# 1u_debug_breakout.net
KiCad netlist of a schematic drawn in EAGLE
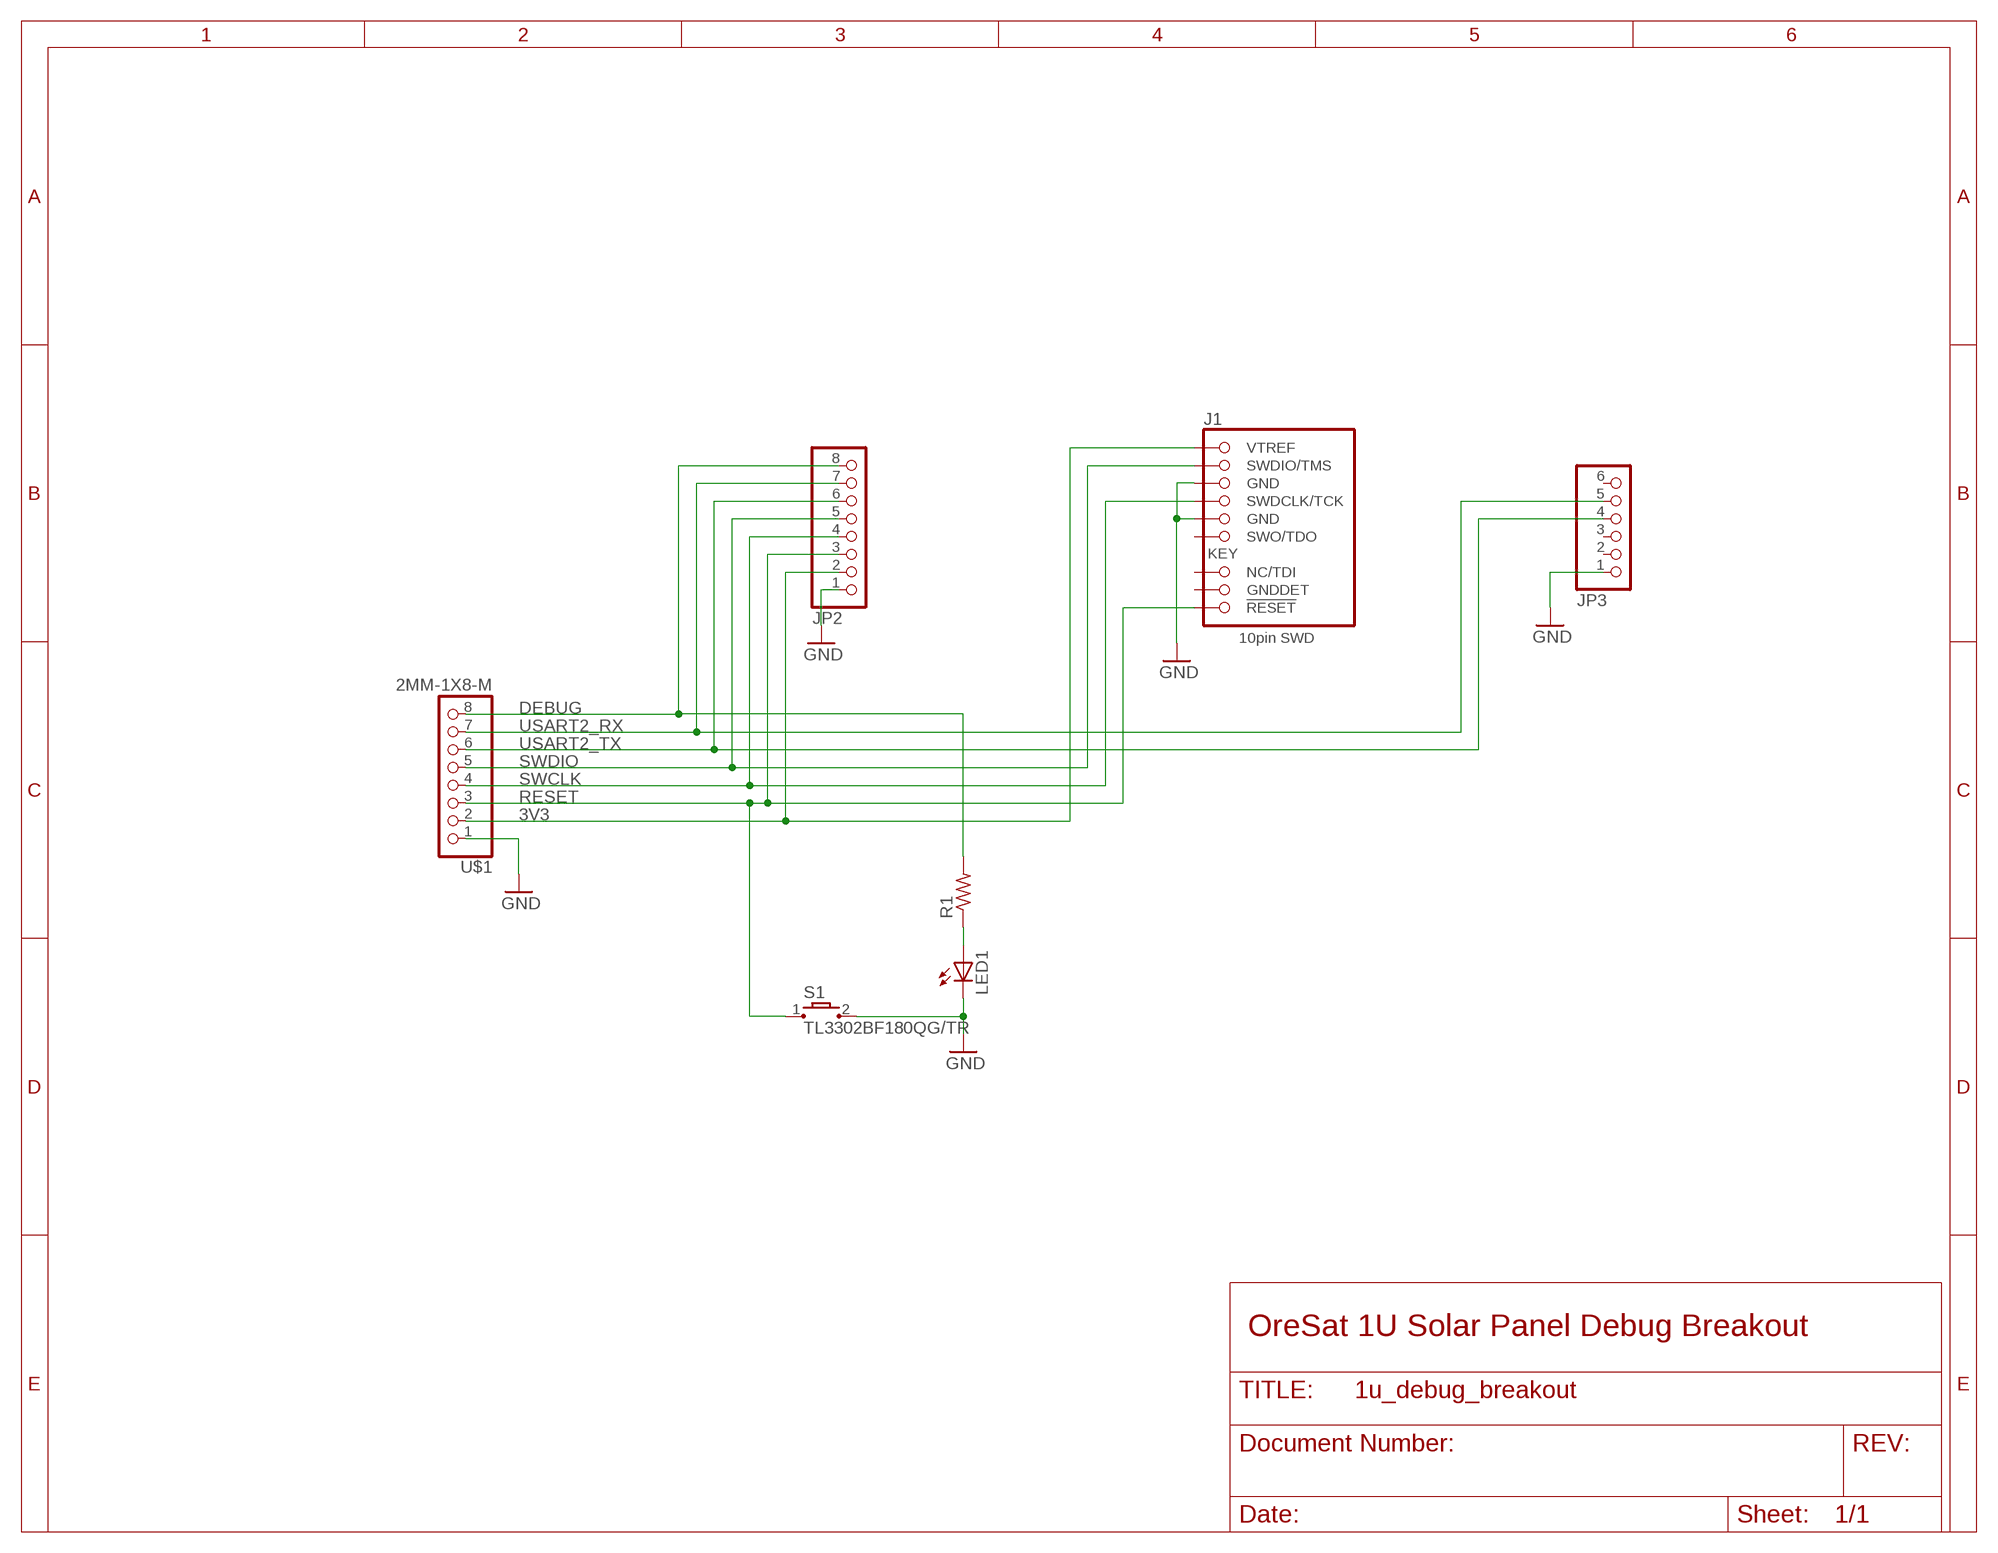
[diagram p0: schematic, sheet 1]

(export (version "E")
  (design (tool "Eeschema 10.0.6"))
  (components
    (comp (ref "J1")
      (value "1.27MM-SWD-CONNECTOR")
      (footprint "eagle-import:1.27MM_2X5")
      (libsource (lib "eagle-import") (part "1.27MM-SWD-CONNECTOR"))
    )
    (comp (ref "JP2")
      (value "PINHD-1X8")
      (footprint "eagle-import:1X08")
      (libsource (lib "eagle-import") (part "PINHD-1X8"))
    )
    (comp (ref "JP3")
      (value "PINHD-1X6")
      (footprint "eagle-import:1X06")
      (libsource (lib "eagle-import") (part "PINHD-1X6"))
    )
    (comp (ref "LED1")
      (value "LEDCHIPLED_0603")
      (footprint "eagle-import:CHIPLED_0603")
      (libsource (lib "eagle-import") (part "LEDCHIPLED_0603"))
    )
    (comp (ref "R1")
      (value "R-US_R0603")
      (footprint "eagle-import:R0603")
      (libsource (lib "eagle-import") (part "R-US_R0603"))
    )
    (comp (ref "S1")
      (value "TL3302BF180QG/TR")
      (footprint "eagle-import:TL3302_GULL_WING")
      (libsource (lib "eagle-import") (part "TL3302-G"))
    )
    (comp (ref "U$1")
      (value "2MM-1X8-M")
      (footprint "eagle-import:CF-2MM-1X8-PRECIDIP-880")
      (libsource (lib "eagle-import") (part "2MM-1X8-M"))
    )
  )
  (nets
    (net (code "1") (name "/3V3") (class "Default")
      (node (ref "J1") (pin "VTREF") (pinfunction "VTREF_VTREF") (pintype "passive"))
      (node (ref "JP2") (pin "2") (pinfunction "2_2") (pintype "passive"))
      (node (ref "U$1") (pin "2") (pinfunction "2_2") (pintype "passive"))
    )
    (net (code "2") (name "/DEBUG") (class "Default")
      (node (ref "JP2") (pin "8") (pinfunction "8_8") (pintype "passive"))
      (node (ref "R1") (pin "2") (pinfunction "2_2") (pintype "passive"))
      (node (ref "U$1") (pin "8") (pinfunction "8_8") (pintype "passive"))
    )
    (net (code "3") (name "/RESET") (class "Default")
      (node (ref "J1") (pin "!RESET") (pinfunction "~{RESET}_!RESET") (pintype "passive"))
      (node (ref "JP2") (pin "3") (pinfunction "3_3") (pintype "passive"))
      (node (ref "S1") (pin "1") (pinfunction "1_1") (pintype "passive"))
      (node (ref "U$1") (pin "3") (pinfunction "3_3") (pintype "passive"))
    )
    (net (code "4") (name "/SWCLK") (class "Default")
      (node (ref "J1") (pin "SWDCLK") (pinfunction "SWDCLK/TCK_SWDCLK") (pintype "passive"))
      (node (ref "JP2") (pin "4") (pinfunction "4_4") (pintype "passive"))
      (node (ref "U$1") (pin "4") (pinfunction "4_4") (pintype "passive"))
    )
    (net (code "5") (name "/SWDIO") (class "Default")
      (node (ref "J1") (pin "SWDIO") (pinfunction "SWDIO/TMS_SWDIO") (pintype "passive"))
      (node (ref "JP2") (pin "5") (pinfunction "5_5") (pintype "passive"))
      (node (ref "U$1") (pin "5") (pinfunction "5_5") (pintype "passive"))
    )
    (net (code "6") (name "/USART2_RX") (class "Default")
      (node (ref "JP2") (pin "7") (pinfunction "7_7") (pintype "passive"))
      (node (ref "JP3") (pin "5") (pinfunction "5_5") (pintype "passive"))
      (node (ref "U$1") (pin "7") (pinfunction "7_7") (pintype "passive"))
    )
    (net (code "7") (name "/USART2_TX") (class "Default")
      (node (ref "JP2") (pin "6") (pinfunction "6_6") (pintype "passive"))
      (node (ref "JP3") (pin "4") (pinfunction "4_4") (pintype "passive"))
      (node (ref "U$1") (pin "6") (pinfunction "6_6") (pintype "passive"))
    )
    (net (code "8") (name "GND") (class "Default")
      (node (ref "J1") (pin "GND") (pinfunction "GND_GND") (pintype "passive"))
      (node (ref "J1") (pin "GND@2") (pinfunction "GND_GND@2") (pintype "passive"))
      (node (ref "JP2") (pin "1") (pinfunction "1_1") (pintype "passive"))
      (node (ref "JP3") (pin "1") (pinfunction "1_1") (pintype "passive"))
      (node (ref "LED1") (pin "C") (pinfunction "C_C") (pintype "passive"))
      (node (ref "S1") (pin "2") (pinfunction "2_2") (pintype "passive"))
      (node (ref "U$1") (pin "1") (pinfunction "1_1") (pintype "passive"))
    )
    (net (code "9") (name "Net-(LED1-PadA)") (class "Default")
      (node (ref "LED1") (pin "A") (pinfunction "A_A") (pintype "passive"))
      (node (ref "R1") (pin "1") (pinfunction "1_1") (pintype "passive"))
    )
    (net (code "10") (name "unconnected-(J1-NC{slash}TDI-PadNC)") (class "Default")
      (node (ref "J1") (pin "NC") (pinfunction "NC/TDI_NC") (pintype "passive"))
    )
    (net (code "11") (name "unconnected-(J1-PadGNDDET)") (class "Default")
      (node (ref "J1") (pin "GNDDET") (pinfunction "GNDDET_GNDDET") (pintype "passive"))
    )
    (net (code "12") (name "unconnected-(J1-SWO{slash}TDO-PadSWO)") (class "Default")
      (node (ref "J1") (pin "SWO") (pinfunction "SWO/TDO_SWO") (pintype "passive"))
    )
    (net (code "13") (name "unconnected-(JP3-Pad2)") (class "Default")
      (node (ref "JP3") (pin "2") (pinfunction "2_2") (pintype "passive"))
    )
    (net (code "14") (name "unconnected-(JP3-Pad3)") (class "Default")
      (node (ref "JP3") (pin "3") (pinfunction "3_3") (pintype "passive"))
    )
    (net (code "15") (name "unconnected-(JP3-Pad6)") (class "Default")
      (node (ref "JP3") (pin "6") (pinfunction "6_6") (pintype "passive"))
    )
  )
)
